# 01_MAIN.net
KiCad netlist of a schematic drawn in Altium Designer
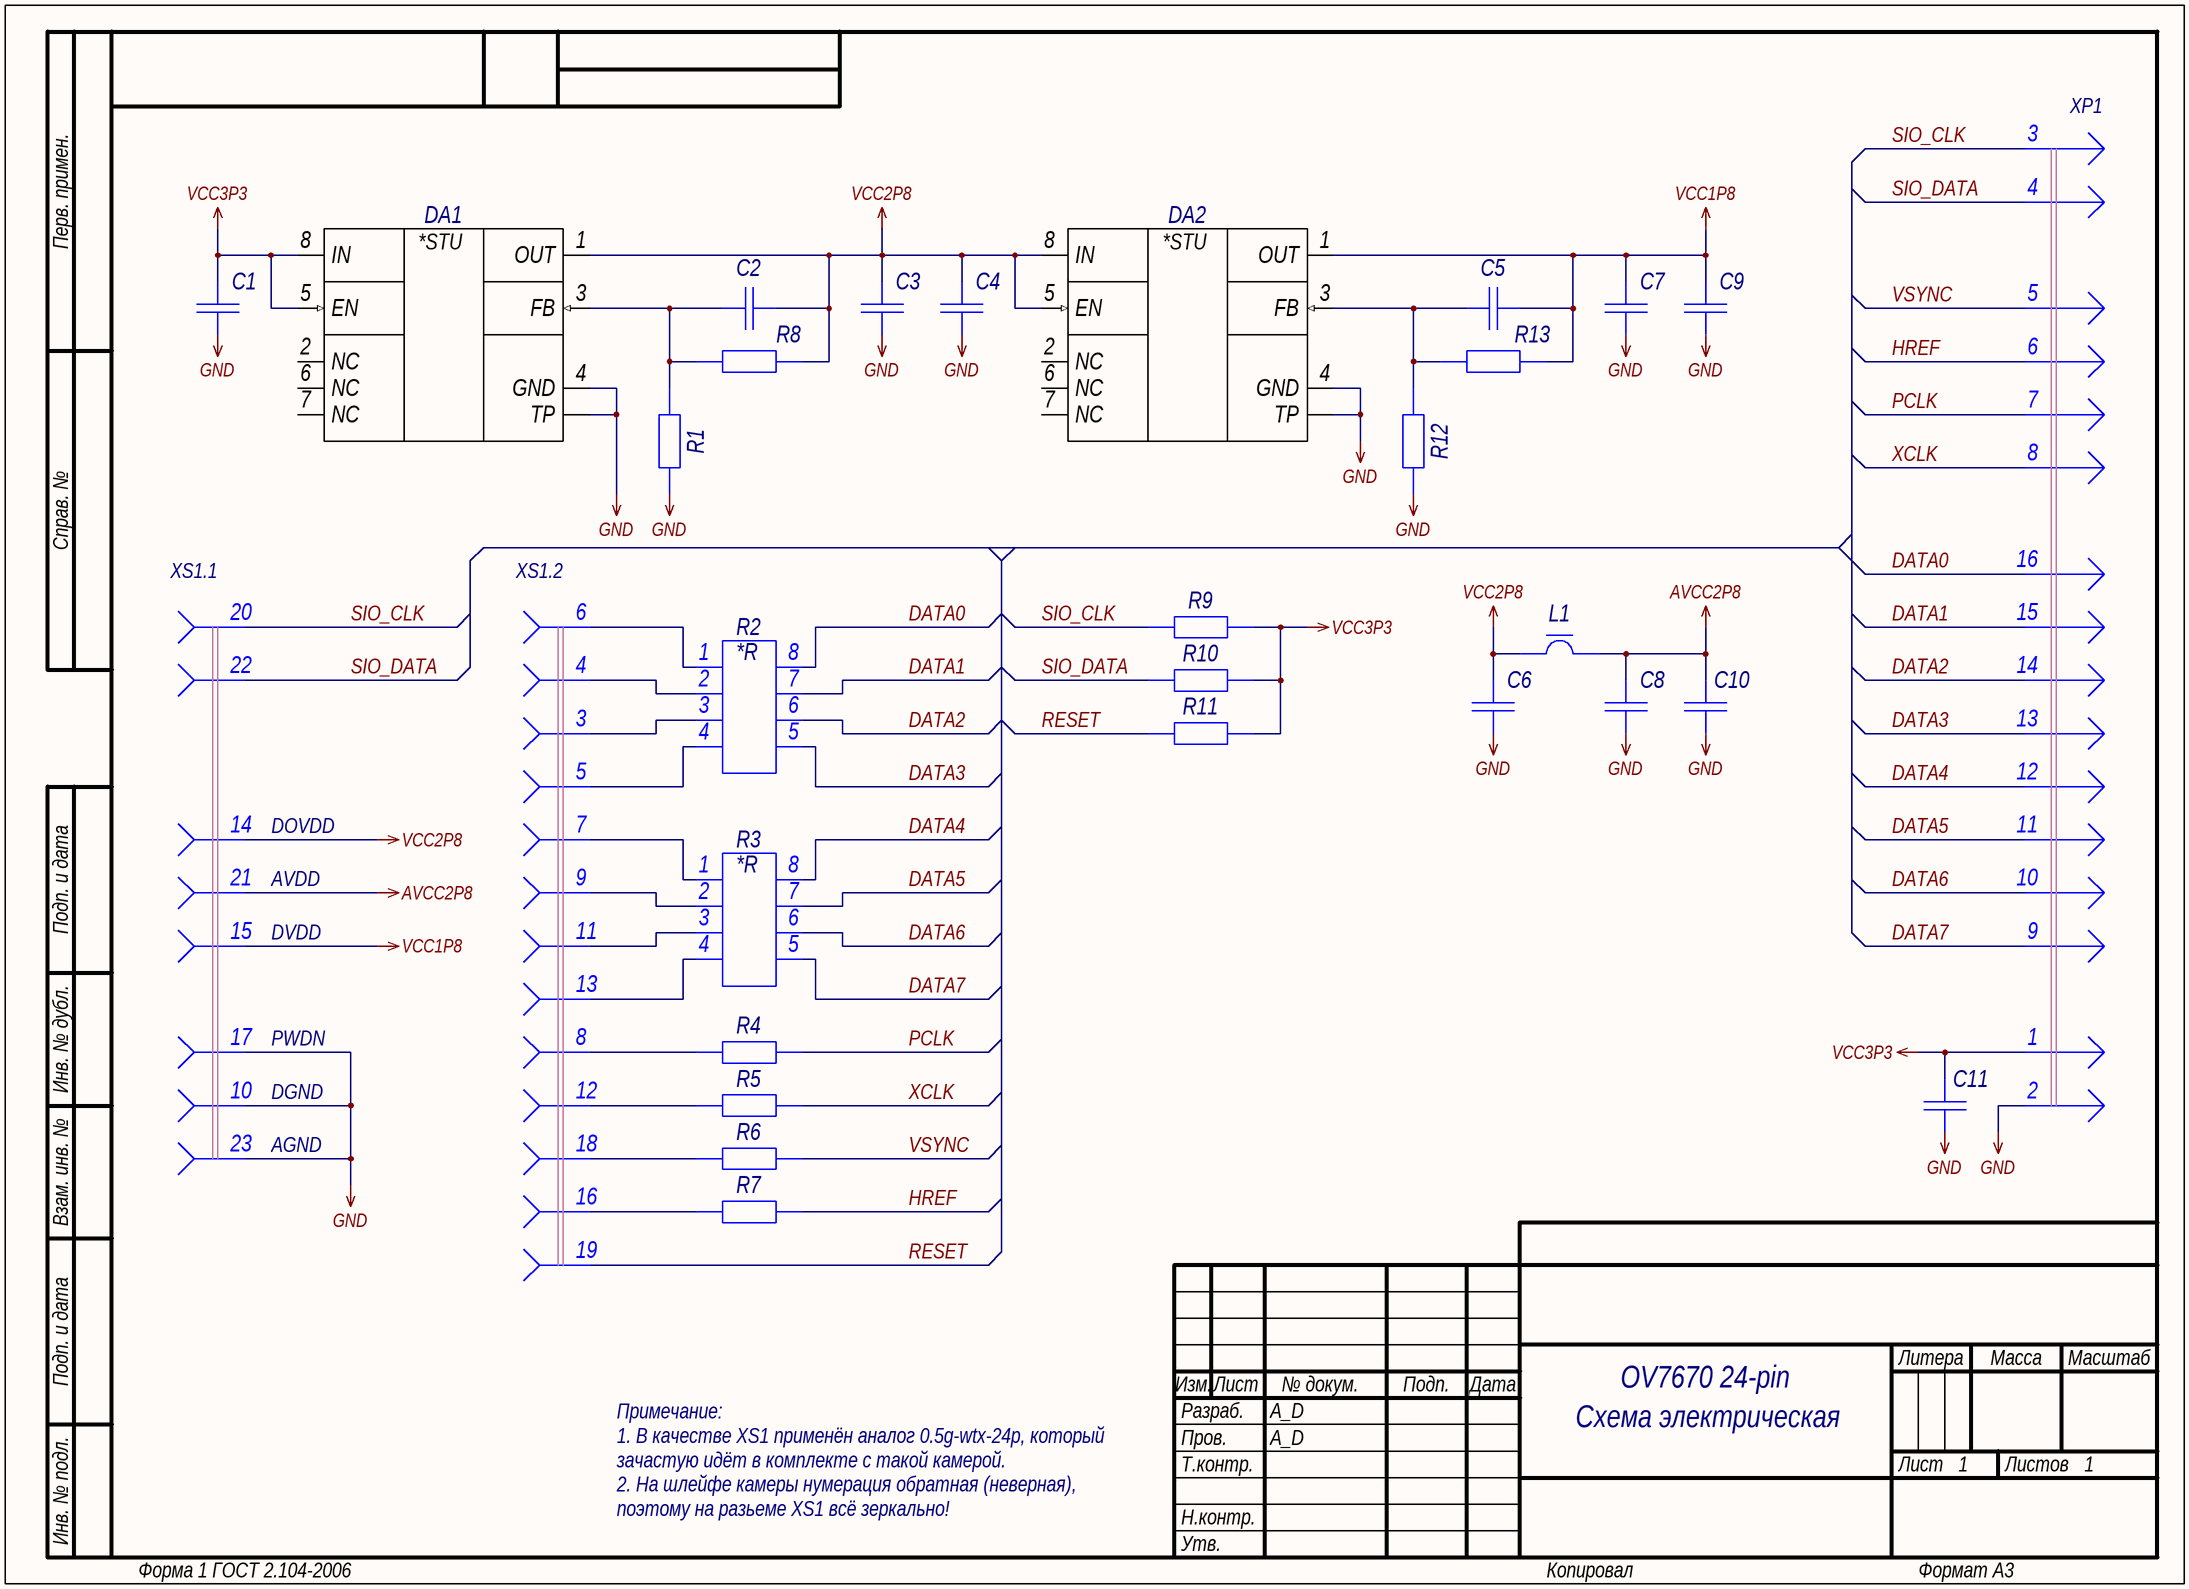
[diagram p0: 01_MAIN.SchDoc]

(export (version "E")
  (design (tool "Eeschema 10.0.6"))
  (components
    (comp (ref "C1")
      (value "Capacitor")
      (footprint "C0603_L")
      (fields
        (field (name "PART NUMBER") "GCM188R71E105KA64D")
        (field (name "VOLTAGE") "25V")
        (field (name "TOLERANCE") "±10%")
        (field (name "PUBLISHER") "Andrew Danich")
      )
      (libsource (lib "ADLib") (part "Capacitor"))
    )
    (comp (ref "C2")
      (value "Capacitor")
      (footprint "C0603_L")
      (fields
        (field (name "PART NUMBER") "GRM1885C1H270JA01D")
        (field (name "VOLTAGE") "50V")
        (field (name "TOLERANCE") "±5%")
        (field (name "PUBLISHER") "Andrew Danich")
      )
      (libsource (lib "ADLib") (part "Capacitor"))
    )
    (comp (ref "C3")
      (value "Capacitor")
      (footprint "C0603_L")
      (fields
        (field (name "PART NUMBER") "GRM188R60J106ME47D")
        (field (name "VOLTAGE") "6.3V")
        (field (name "TOLERANCE") "±20%")
        (field (name "PUBLISHER") "Andrew Danich")
      )
      (libsource (lib "ADLib") (part "Capacitor"))
    )
    (comp (ref "C4")
      (value "Capacitor")
      (footprint "C0603_L")
      (fields
        (field (name "PART NUMBER") "GRM188R72A104KA35D")
        (field (name "VOLTAGE") "100V")
        (field (name "TOLERANCE") "±10%")
        (field (name "PUBLISHER") "Andrew Danich")
      )
      (libsource (lib "ADLib") (part "Capacitor"))
    )
    (comp (ref "C5")
      (value "Capacitor")
      (footprint "C0603_L")
      (fields
        (field (name "PART NUMBER") "GRM1885C1H270JA01D")
        (field (name "VOLTAGE") "50V")
        (field (name "TOLERANCE") "±5%")
        (field (name "PUBLISHER") "Andrew Danich")
      )
      (libsource (lib "ADLib") (part "Capacitor"))
    )
    (comp (ref "C6")
      (value "Capacitor")
      (footprint "C0603_L")
      (fields
        (field (name "PART NUMBER") "GRM188R72A104KA35D")
        (field (name "VOLTAGE") "100V")
        (field (name "TOLERANCE") "±10%")
        (field (name "PUBLISHER") "Andrew Danich")
      )
      (libsource (lib "ADLib") (part "Capacitor"))
    )
    (comp (ref "C7")
      (value "Capacitor")
      (footprint "C0603_L")
      (fields
        (field (name "PART NUMBER") "GRM188R60J106ME47D")
        (field (name "VOLTAGE") "6.3V")
        (field (name "TOLERANCE") "±20%")
        (field (name "PUBLISHER") "Andrew Danich")
      )
      (libsource (lib "ADLib") (part "Capacitor"))
    )
    (comp (ref "C8")
      (value "Capacitor")
      (footprint "C0603_L")
      (fields
        (field (name "PART NUMBER") "GRT188C81E475KE13D")
        (field (name "VOLTAGE") "25V")
        (field (name "TOLERANCE") "±20%")
        (field (name "PUBLISHER") "Andrew Danich")
      )
      (libsource (lib "ADLib") (part "Capacitor"))
    )
    (comp (ref "C9")
      (value "Capacitor")
      (footprint "C0603_L")
      (fields
        (field (name "PART NUMBER") "GRM188R72A104KA35D")
        (field (name "VOLTAGE") "100V")
        (field (name "TOLERANCE") "±10%")
        (field (name "PUBLISHER") "Andrew Danich")
      )
      (libsource (lib "ADLib") (part "Capacitor"))
    )
    (comp (ref "C10")
      (value "Capacitor")
      (footprint "C0603_L")
      (fields
        (field (name "PART NUMBER") "GRM188R72A104KA35D")
        (field (name "VOLTAGE") "100V")
        (field (name "TOLERANCE") "±10%")
        (field (name "PUBLISHER") "Andrew Danich")
      )
      (libsource (lib "ADLib") (part "Capacitor"))
    )
    (comp (ref "C11")
      (value "Capacitor")
      (footprint "C0603_L")
      (fields
        (field (name "PART NUMBER") "GRM188R60J106ME47D")
        (field (name "VOLTAGE") "6.3V")
        (field (name "TOLERANCE") "±20%")
        (field (name "PUBLISHER") "Andrew Danich")
      )
      (libsource (lib "ADLib") (part "Capacitor"))
    )
    (comp (ref "DA1")
      (value "TPS73501DRB")
      (footprint "VSON-8_065P300X300X100_N")
      (fields
        (field (name "PART NUMBER") "TPS73501DRBR")
        (field (name "MANUFACTURER") "Texas Instruments")
        (field (name "PUBLISHER") "Andrew Danich")
      )
      (libsource (lib "ADLib") (part "TPS73501DRB"))
    )
    (comp (ref "DA2")
      (value "TPS73501DRB")
      (footprint "VSON-8_065P300X300X100_N")
      (fields
        (field (name "PART NUMBER") "TPS73501DRBR")
        (field (name "MANUFACTURER") "Texas Instruments")
        (field (name "PUBLISHER") "Andrew Danich")
      )
      (libsource (lib "ADLib") (part "TPS73501DRB"))
    )
    (comp (ref "L1")
      (value "FerriteBead")
      (footprint "L0603_L")
      (fields
        (field (name "PART NUMBER") "BLM18PG121SN1")
        (field (name "TOLERANCE") "±25%")
        (field (name "MANUFACTURER") "Murata")
        (field (name "PUBLISHER") "Andrew Danich")
      )
      (libsource (lib "ADLib") (part "FerriteBead"))
    )
    (comp (ref "R1")
      (value "Resistor")
      (footprint "R0603_L")
      (fields
        (field (name "PART NUMBER") "RC0603FR-0775KL")
        (field (name "TOLERANCE") "±1%")
        (field (name "MANUFACTURER") "Yageo")
        (field (name "PUBLISHER") "Andrew Danich")
      )
      (libsource (lib "ADLib") (part "Resistor"))
    )
    (comp (ref "R2")
      (value "Resistor-4")
      (footprint "CAT16-x4")
      (fields
        (field (name "PART NUMBER") "TC164-JR-0751RL")
        (field (name "TOLERANCE") "±5%")
        (field (name "MANUFACTURER") "Yageo")
        (field (name "PUBLISHER") "Andrew Danich")
      )
      (libsource (lib "ADLib") (part "Resistor-4"))
    )
    (comp (ref "R3")
      (value "Resistor-4")
      (footprint "CAT16-x4")
      (fields
        (field (name "PART NUMBER") "TC164-JR-0751RL")
        (field (name "TOLERANCE") "±5%")
        (field (name "MANUFACTURER") "Yageo")
        (field (name "PUBLISHER") "Andrew Danich")
      )
      (libsource (lib "ADLib") (part "Resistor-4"))
    )
    (comp (ref "R4")
      (value "Resistor")
      (footprint "R0603_L")
      (fields
        (field (name "PART NUMBER") "RC0603JR-0751RL")
        (field (name "TOLERANCE") "±5%")
        (field (name "MANUFACTURER") "Yageo")
        (field (name "PUBLISHER") "Andrew Danich")
      )
      (libsource (lib "ADLib") (part "Resistor"))
    )
    (comp (ref "R5")
      (value "Resistor")
      (footprint "R0603_L")
      (fields
        (field (name "PART NUMBER") "RC0603JR-0751RL")
        (field (name "TOLERANCE") "±5%")
        (field (name "MANUFACTURER") "Yageo")
        (field (name "PUBLISHER") "Andrew Danich")
      )
      (libsource (lib "ADLib") (part "Resistor"))
    )
    (comp (ref "R6")
      (value "Resistor")
      (footprint "R0603_L")
      (fields
        (field (name "PART NUMBER") "RC0603JR-0751RL")
        (field (name "TOLERANCE") "±5%")
        (field (name "MANUFACTURER") "Yageo")
        (field (name "PUBLISHER") "Andrew Danich")
      )
      (libsource (lib "ADLib") (part "Resistor"))
    )
    (comp (ref "R7")
      (value "Resistor")
      (footprint "R0603_L")
      (fields
        (field (name "PART NUMBER") "RC0603JR-0751RL")
        (field (name "TOLERANCE") "±5%")
        (field (name "MANUFACTURER") "Yageo")
        (field (name "PUBLISHER") "Andrew Danich")
      )
      (libsource (lib "ADLib") (part "Resistor"))
    )
    (comp (ref "R8")
      (value "Resistor")
      (footprint "R0603_L")
      (fields
        (field (name "PART NUMBER") "RC0603FR-07100KL")
        (field (name "TOLERANCE") "±1%")
        (field (name "MANUFACTURER") "Yageo")
        (field (name "PUBLISHER") "Andrew Danich")
      )
      (libsource (lib "ADLib") (part "Resistor"))
    )
    (comp (ref "R9")
      (value "Resistor")
      (footprint "R0603_L")
      (fields
        (field (name "PART NUMBER") "RC0603JR-074K7L")
        (field (name "TOLERANCE") "±5%")
        (field (name "MANUFACTURER") "Yageo")
        (field (name "PUBLISHER") "Andrew Danich")
      )
      (libsource (lib "ADLib") (part "Resistor"))
    )
    (comp (ref "R10")
      (value "Resistor")
      (footprint "R0603_L")
      (fields
        (field (name "PART NUMBER") "RC0603JR-074K7L")
        (field (name "TOLERANCE") "±5%")
        (field (name "MANUFACTURER") "Yageo")
        (field (name "PUBLISHER") "Andrew Danich")
      )
      (libsource (lib "ADLib") (part "Resistor"))
    )
    (comp (ref "R11")
      (value "Resistor")
      (footprint "R0603_L")
      (fields
        (field (name "PART NUMBER") "RC0603JR-074K7L")
        (field (name "TOLERANCE") "±5%")
        (field (name "MANUFACTURER") "Yageo")
        (field (name "PUBLISHER") "Andrew Danich")
      )
      (libsource (lib "ADLib") (part "Resistor"))
    )
    (comp (ref "R12")
      (value "Resistor")
      (footprint "R0603_L")
      (fields
        (field (name "PART NUMBER") "RC0603FR-07200KL")
        (field (name "TOLERANCE") "±1%")
        (field (name "MANUFACTURER") "Yageo")
        (field (name "PUBLISHER") "Andrew Danich")
      )
      (libsource (lib "ADLib") (part "Resistor"))
    )
    (comp (ref "R13")
      (value "Resistor")
      (footprint "R0603_L")
      (fields
        (field (name "PART NUMBER") "RC0603FR-07100KL")
        (field (name "TOLERANCE") "±1%")
        (field (name "MANUFACTURER") "Yageo")
        (field (name "PUBLISHER") "Andrew Danich")
      )
      (libsource (lib "ADLib") (part "Resistor"))
    )
    (comp (ref "WW1")
      (value "NoBody")
      (footprint "MH_M2.5")
      (fields (field (name "PART NUMBER") "MOUNTINGHOLE") (field (name "PUBLISHER") "Andrew Danich"))
      (libsource (lib "ADLib") (part "NoBody"))
    )
    (comp (ref "WW2")
      (value "NoBody")
      (footprint "MH_M2.5")
      (fields (field (name "PART NUMBER") "MOUNTINGHOLE") (field (name "PUBLISHER") "Andrew Danich"))
      (libsource (lib "ADLib") (part "NoBody"))
    )
    (comp (ref "XP1")
      (value "Text")
      (footprint "PLD-16")
      (fields (field (name "PART NUMBER") "PLD-16") (field (name "PUBLISHER") "НТЦ \"Вектор\""))
      (libsource (lib "ADLib") (part "Con-16-M_S"))
    )
    (comp (ref "XS1")
      (value "OV7670")
      (footprint "FH12-24S-0.5SH")
      (fields
        (field (name "PART NUMBER") "FH12-24S-0.5SH(55)")
        (field (name "MANUFACTURER") "Hirose Connector")
        (field (name "PUBLISHER") "Andrew Danich")
      )
      (libsource (lib "ADLib") (part "Con-24-F_S"))
    )
  )
  (nets
    (net (code "1") (name "/DATA0") (class "Default")
      (node (ref "R2") (pin "8") (pintype "passive"))
      (node (ref "XP1") (pin "16") (pintype "passive"))
    )
    (net (code "2") (name "/DATA1") (class "Default")
      (node (ref "R2") (pin "7") (pintype "passive"))
      (node (ref "XP1") (pin "15") (pintype "passive"))
    )
    (net (code "3") (name "/DATA2") (class "Default")
      (node (ref "R2") (pin "6") (pintype "passive"))
      (node (ref "XP1") (pin "14") (pintype "passive"))
    )
    (net (code "4") (name "/DATA3") (class "Default")
      (node (ref "R2") (pin "5") (pintype "passive"))
      (node (ref "XP1") (pin "13") (pintype "passive"))
    )
    (net (code "5") (name "/DATA4") (class "Default")
      (node (ref "R3") (pin "8") (pintype "passive"))
      (node (ref "XP1") (pin "12") (pintype "passive"))
    )
    (net (code "6") (name "/DATA5") (class "Default")
      (node (ref "R3") (pin "7") (pintype "passive"))
      (node (ref "XP1") (pin "11") (pintype "passive"))
    )
    (net (code "7") (name "/DATA6") (class "Default")
      (node (ref "R3") (pin "6") (pintype "passive"))
      (node (ref "XP1") (pin "10") (pintype "passive"))
    )
    (net (code "8") (name "/DATA7") (class "Default")
      (node (ref "R3") (pin "5") (pintype "passive"))
      (node (ref "XP1") (pin "9") (pintype "passive"))
    )
    (net (code "9") (name "/HREF") (class "Default")
      (node (ref "R7") (pin "2") (pinfunction "2_2") (pintype "passive"))
      (node (ref "XP1") (pin "6") (pintype "passive"))
    )
    (net (code "10") (name "/PCLK") (class "Default")
      (node (ref "R4") (pin "2") (pinfunction "2_2") (pintype "passive"))
      (node (ref "XP1") (pin "7") (pintype "passive"))
    )
    (net (code "11") (name "/RESET") (class "Default")
      (node (ref "R11") (pin "1") (pinfunction "1_1") (pintype "passive"))
      (node (ref "XS1") (pin "19") (pintype "passive"))
    )
    (net (code "12") (name "/SIO_CLK") (class "Default")
      (node (ref "R9") (pin "1") (pinfunction "1_1") (pintype "passive"))
      (node (ref "XP1") (pin "3") (pintype "passive"))
      (node (ref "XS1") (pin "20") (pintype "passive"))
    )
    (net (code "13") (name "/SIO_DATA") (class "Default")
      (node (ref "R10") (pin "1") (pinfunction "1_1") (pintype "passive"))
      (node (ref "XP1") (pin "4") (pintype "passive"))
      (node (ref "XS1") (pin "22") (pintype "passive"))
    )
    (net (code "14") (name "/VSYNC") (class "Default")
      (node (ref "R6") (pin "2") (pinfunction "2_2") (pintype "passive"))
      (node (ref "XP1") (pin "5") (pintype "passive"))
    )
    (net (code "15") (name "/XCLK") (class "Default")
      (node (ref "R5") (pin "2") (pinfunction "2_2") (pintype "passive"))
      (node (ref "XP1") (pin "8") (pintype "passive"))
    )
    (net (code "16") (name "AVCC2P8") (class "Default")
      (node (ref "C10") (pin "2") (pinfunction "2_2") (pintype "passive"))
      (node (ref "C8") (pin "2") (pinfunction "2_2") (pintype "passive"))
      (node (ref "L1") (pin "2") (pinfunction "2_2") (pintype "passive"))
      (node (ref "XS1") (pin "21") (pintype "passive"))
    )
    (net (code "17") (name "GND") (class "Default")
      (node (ref "C1") (pin "1") (pinfunction "1_1") (pintype "passive"))
      (node (ref "C10") (pin "1") (pinfunction "1_1") (pintype "passive"))
      (node (ref "C11") (pin "1") (pinfunction "1_1") (pintype "passive"))
      (node (ref "C3") (pin "1") (pinfunction "1_1") (pintype "passive"))
      (node (ref "C4") (pin "1") (pinfunction "1_1") (pintype "passive"))
      (node (ref "C6") (pin "1") (pinfunction "1_1") (pintype "passive"))
      (node (ref "C7") (pin "1") (pinfunction "1_1") (pintype "passive"))
      (node (ref "C8") (pin "1") (pinfunction "1_1") (pintype "passive"))
      (node (ref "C9") (pin "1") (pinfunction "1_1") (pintype "passive"))
      (node (ref "DA1") (pin "4") (pinfunction "GND_4") (pintype "power_in"))
      (node (ref "DA1") (pin "TP") (pinfunction "TP_TP") (pintype "passive"))
      (node (ref "DA2") (pin "4") (pinfunction "GND_4") (pintype "power_in"))
      (node (ref "DA2") (pin "TP") (pinfunction "TP_TP") (pintype "passive"))
      (node (ref "R1") (pin "1") (pinfunction "1_1") (pintype "passive"))
      (node (ref "R12") (pin "1") (pinfunction "1_1") (pintype "passive"))
      (node (ref "XP1") (pin "2") (pintype "passive"))
      (node (ref "XS1") (pin "10") (pintype "passive"))
      (node (ref "XS1") (pin "17") (pintype "passive"))
      (node (ref "XS1") (pin "23") (pintype "passive"))
    )
    (net (code "18") (name "Net-(DA1-FB)") (class "Default")
      (node (ref "C2") (pin "1") (pinfunction "1_1") (pintype "passive"))
      (node (ref "DA1") (pin "3") (pinfunction "FB_3") (pintype "input"))
      (node (ref "R1") (pin "2") (pinfunction "2_2") (pintype "passive"))
      (node (ref "R8") (pin "1") (pinfunction "1_1") (pintype "passive"))
    )
    (net (code "19") (name "Net-(DA2-FB)") (class "Default")
      (node (ref "C5") (pin "1") (pinfunction "1_1") (pintype "passive"))
      (node (ref "DA2") (pin "3") (pinfunction "FB_3") (pintype "input"))
      (node (ref "R12") (pin "2") (pinfunction "2_2") (pintype "passive"))
      (node (ref "R13") (pin "1") (pinfunction "1_1") (pintype "passive"))
    )
    (net (code "20") (name "Net-(R2-Pad1)") (class "Default")
      (node (ref "R2") (pin "1") (pintype "passive"))
      (node (ref "XS1") (pin "6") (pintype "passive"))
    )
    (net (code "21") (name "Net-(R2-Pad2)") (class "Default")
      (node (ref "R2") (pin "2") (pintype "passive"))
      (node (ref "XS1") (pin "4") (pintype "passive"))
    )
    (net (code "22") (name "Net-(R2-Pad3)") (class "Default")
      (node (ref "R2") (pin "3") (pintype "passive"))
      (node (ref "XS1") (pin "3") (pintype "passive"))
    )
    (net (code "23") (name "Net-(R2-Pad4)") (class "Default")
      (node (ref "R2") (pin "4") (pintype "passive"))
      (node (ref "XS1") (pin "5") (pintype "passive"))
    )
    (net (code "24") (name "Net-(R3-Pad1)") (class "Default")
      (node (ref "R3") (pin "1") (pintype "passive"))
      (node (ref "XS1") (pin "7") (pintype "passive"))
    )
    (net (code "25") (name "Net-(R3-Pad2)") (class "Default")
      (node (ref "R3") (pin "2") (pintype "passive"))
      (node (ref "XS1") (pin "9") (pintype "passive"))
    )
    (net (code "26") (name "Net-(R3-Pad3)") (class "Default")
      (node (ref "R3") (pin "3") (pintype "passive"))
      (node (ref "XS1") (pin "11") (pintype "passive"))
    )
    (net (code "27") (name "Net-(R3-Pad4)") (class "Default")
      (node (ref "R3") (pin "4") (pintype "passive"))
      (node (ref "XS1") (pin "13") (pintype "passive"))
    )
    (net (code "28") (name "Net-(R4-Pad1)") (class "Default")
      (node (ref "R4") (pin "1") (pinfunction "1_1") (pintype "passive"))
      (node (ref "XS1") (pin "8") (pintype "passive"))
    )
    (net (code "29") (name "Net-(R5-Pad1)") (class "Default")
      (node (ref "R5") (pin "1") (pinfunction "1_1") (pintype "passive"))
      (node (ref "XS1") (pin "12") (pintype "passive"))
    )
    (net (code "30") (name "Net-(R6-Pad1)") (class "Default")
      (node (ref "R6") (pin "1") (pinfunction "1_1") (pintype "passive"))
      (node (ref "XS1") (pin "18") (pintype "passive"))
    )
    (net (code "31") (name "Net-(R7-Pad1)") (class "Default")
      (node (ref "R7") (pin "1") (pinfunction "1_1") (pintype "passive"))
      (node (ref "XS1") (pin "16") (pintype "passive"))
    )
    (net (code "32") (name "VCC1P8") (class "Default")
      (node (ref "C5") (pin "2") (pinfunction "2_2") (pintype "passive"))
      (node (ref "C7") (pin "2") (pinfunction "2_2") (pintype "passive"))
      (node (ref "C9") (pin "2") (pinfunction "2_2") (pintype "passive"))
      (node (ref "DA2") (pin "1") (pinfunction "OUT_1") (pintype "power_in"))
      (node (ref "R13") (pin "2") (pinfunction "2_2") (pintype "passive"))
      (node (ref "XS1") (pin "15") (pintype "passive"))
    )
    (net (code "33") (name "VCC2P8") (class "Default")
      (node (ref "C2") (pin "2") (pinfunction "2_2") (pintype "passive"))
      (node (ref "C3") (pin "2") (pinfunction "2_2") (pintype "passive"))
      (node (ref "C4") (pin "2") (pinfunction "2_2") (pintype "passive"))
      (node (ref "C6") (pin "2") (pinfunction "2_2") (pintype "passive"))
      (node (ref "DA1") (pin "1") (pinfunction "OUT_1") (pintype "power_in"))
      (node (ref "DA2") (pin "5") (pinfunction "EN_5") (pintype "input"))
      (node (ref "DA2") (pin "8") (pinfunction "IN_8") (pintype "power_in"))
      (node (ref "L1") (pin "1") (pinfunction "1_1") (pintype "passive"))
      (node (ref "R8") (pin "2") (pinfunction "2_2") (pintype "passive"))
      (node (ref "XS1") (pin "14") (pintype "passive"))
    )
    (net (code "34") (name "VCC3P3") (class "Default")
      (node (ref "C1") (pin "2") (pinfunction "2_2") (pintype "passive"))
      (node (ref "C11") (pin "2") (pinfunction "2_2") (pintype "passive"))
      (node (ref "DA1") (pin "5") (pinfunction "EN_5") (pintype "input"))
      (node (ref "DA1") (pin "8") (pinfunction "IN_8") (pintype "power_in"))
      (node (ref "R10") (pin "2") (pinfunction "2_2") (pintype "passive"))
      (node (ref "R11") (pin "2") (pinfunction "2_2") (pintype "passive"))
      (node (ref "R9") (pin "2") (pinfunction "2_2") (pintype "passive"))
      (node (ref "XP1") (pin "1") (pintype "passive"))
    )
    (net (code "35") (name "unconnected-(DA1-NC-Pad2)") (class "Default")
      (node (ref "DA1") (pin "2") (pinfunction "NC_2") (pintype "passive"))
    )
    (net (code "36") (name "unconnected-(DA1-NC-Pad6)") (class "Default")
      (node (ref "DA1") (pin "6") (pinfunction "NC_6") (pintype "passive"))
    )
    (net (code "37") (name "unconnected-(DA1-NC-Pad7)") (class "Default")
      (node (ref "DA1") (pin "7") (pinfunction "NC_7") (pintype "passive"))
    )
    (net (code "38") (name "unconnected-(DA2-NC-Pad2)") (class "Default")
      (node (ref "DA2") (pin "2") (pinfunction "NC_2") (pintype "passive"))
    )
    (net (code "39") (name "unconnected-(DA2-NC-Pad6)") (class "Default")
      (node (ref "DA2") (pin "6") (pinfunction "NC_6") (pintype "passive"))
    )
    (net (code "40") (name "unconnected-(DA2-NC-Pad7)") (class "Default")
      (node (ref "DA2") (pin "7") (pinfunction "NC_7") (pintype "passive"))
    )
  )
)
